# SimGEKI2_Side.net
KiCad netlist of a schematic drawn in EasyEDA Pro
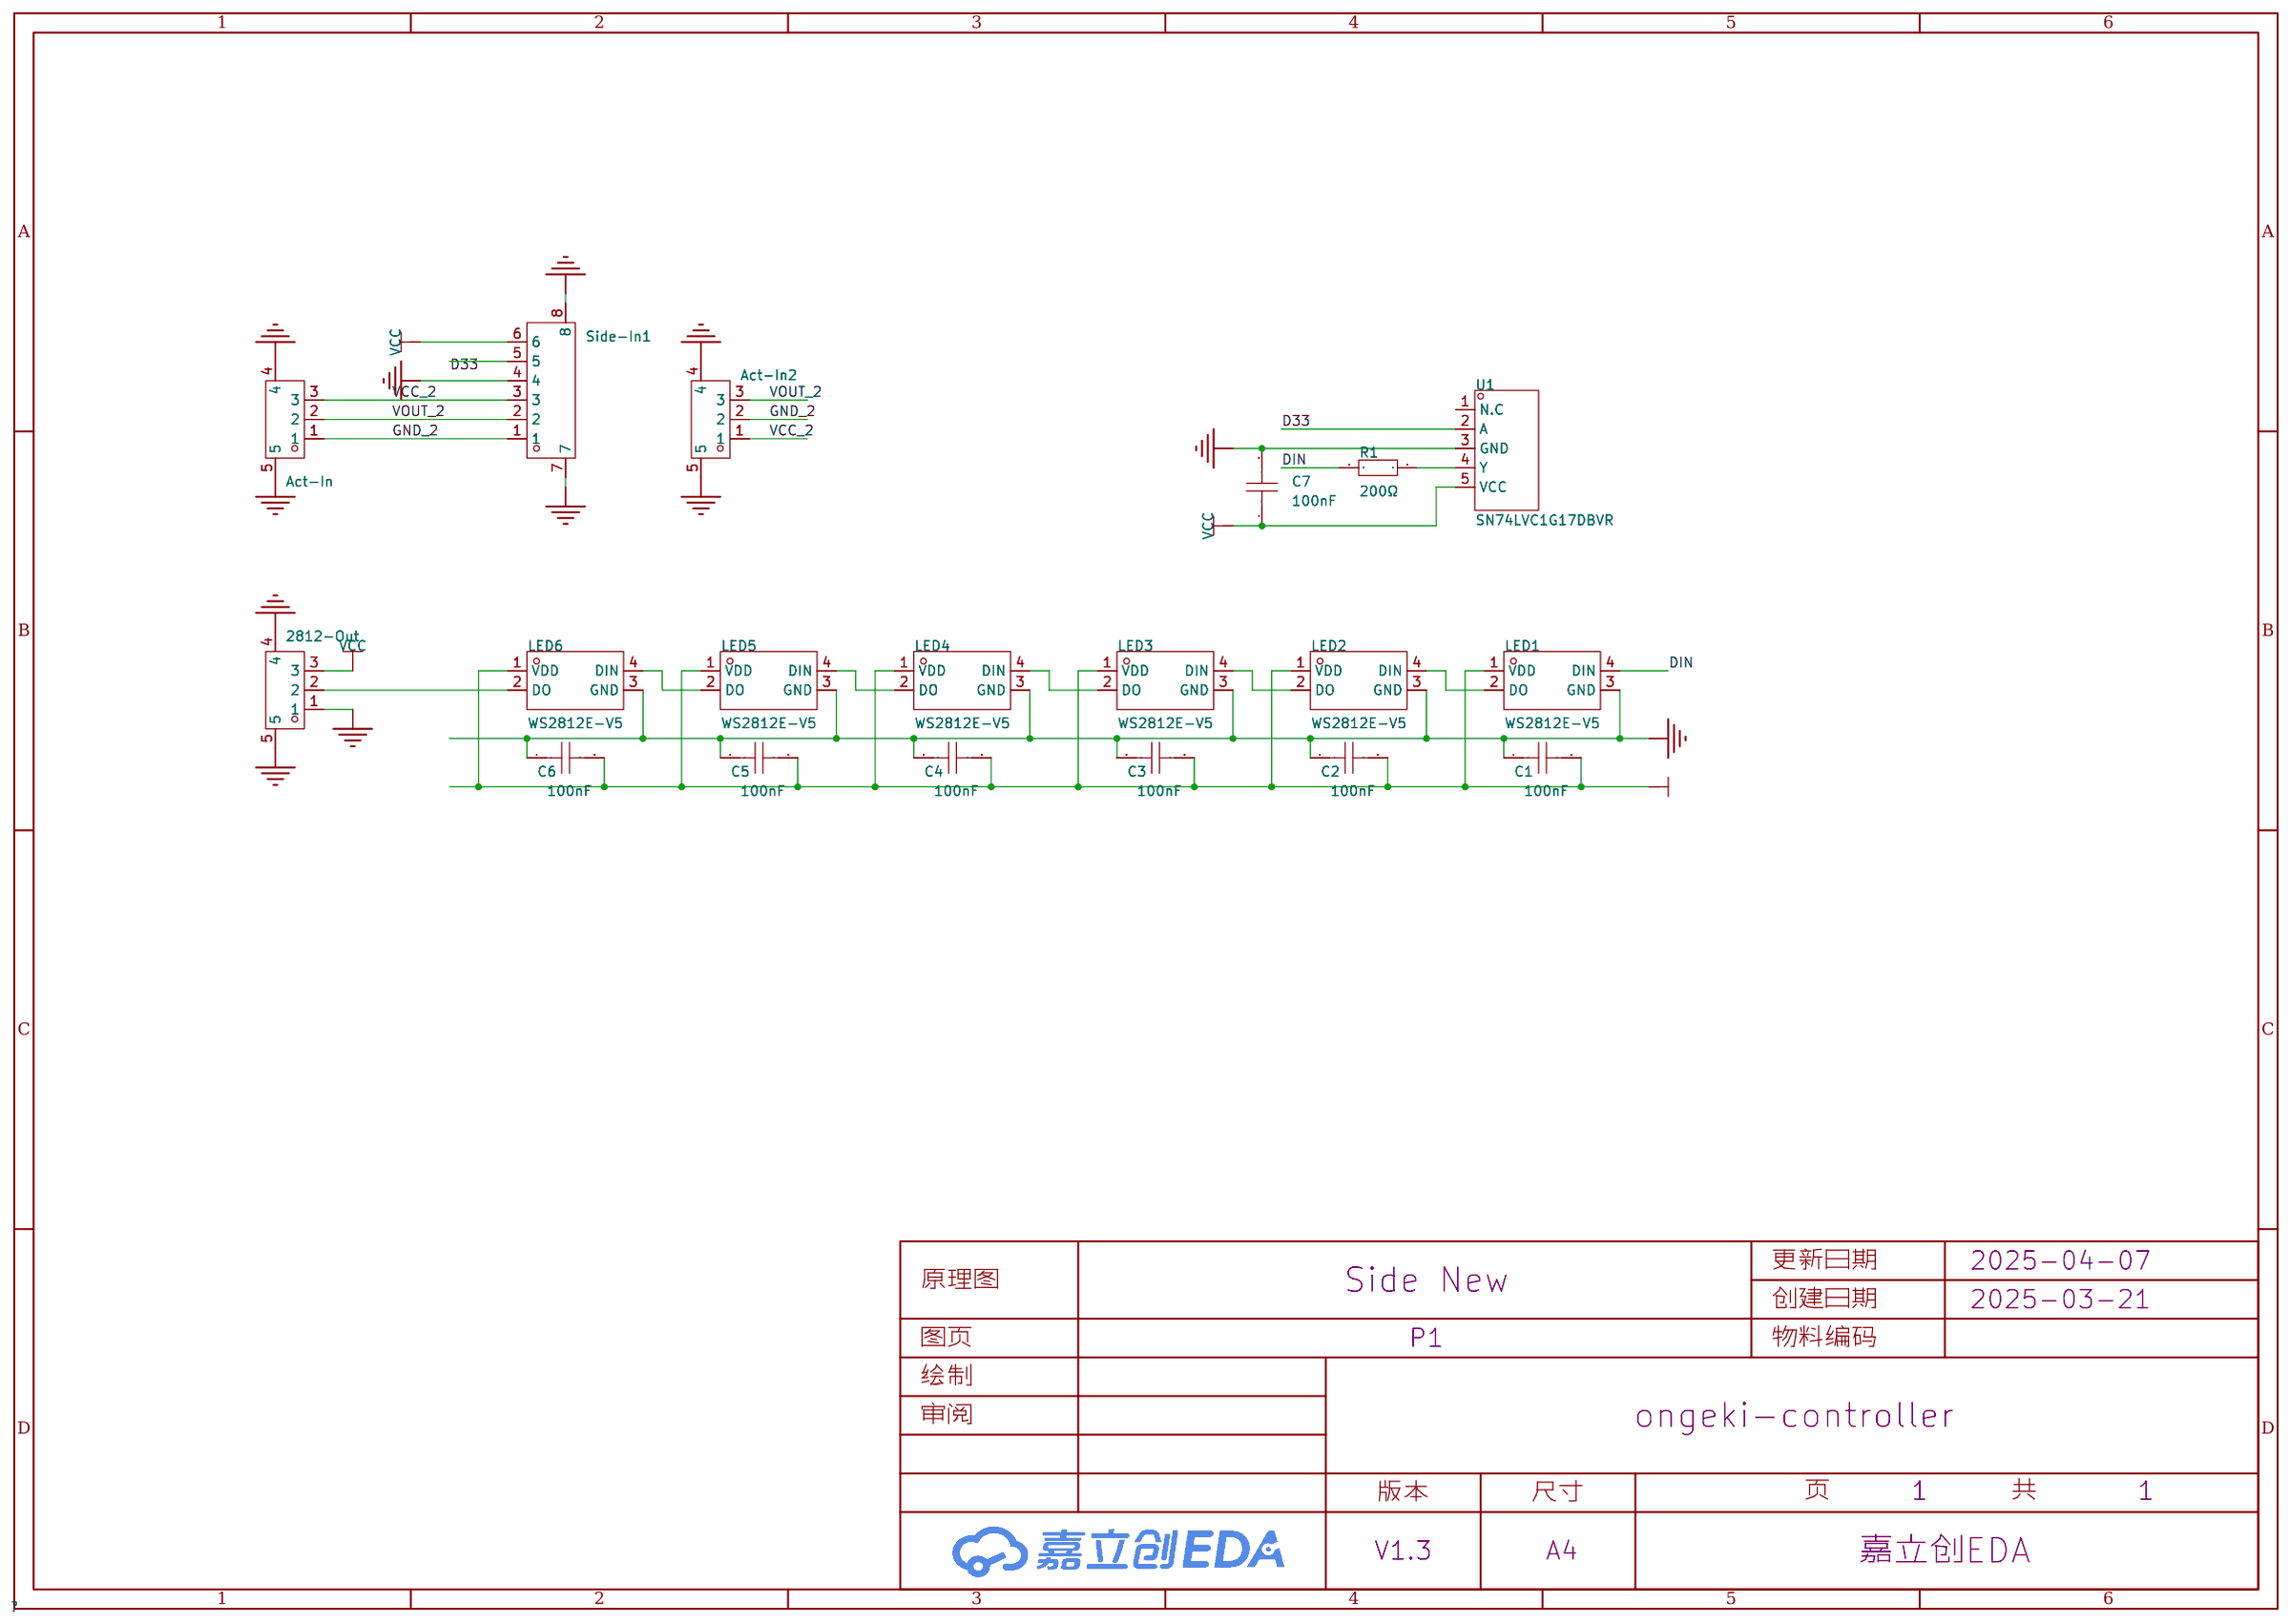
[diagram p0: schematic sheet]

(export (version "E")
  (design (tool "Eeschema 10.0.6"))
  (components
    (comp (ref "2812-Out")
      (value "WAFER-PH2.0-3PWB")
      (footprint "easyedapro:CONN-SMD_3P-P2.00_XUNPU_WAFER-PH2.0-3PWB")
      (description "插针结构:1x3P;间距:2mm;安装方式:卧贴;总PIN数:3P;排数:1;每排PIN数:3;额定电流:2A;工作温度范围:-25°C~+85°C;")
      (fields (field (name "Manufacturer") "XUNPU(讯普)"))
      (libsource (lib "easyedapro") (part "WAFER-PH2.0-3PWB"))
    )
    (comp (ref "Act-In")
      (value "WAFER-PH2.0-3PWB")
      (footprint "easyedapro:CONN-SMD_3P-P2.00_XUNPU_WAFER-PH2.0-3PWB")
      (description "插针结构:1x3P;间距:2mm;安装方式:卧贴;总PIN数:3P;排数:1;每排PIN数:3;额定电流:2A;工作温度范围:-25°C~+85°C;")
      (fields (field (name "Manufacturer") "XUNPU(讯普)"))
      (libsource (lib "easyedapro") (part "WAFER-PH2.0-3PWB"))
    )
    (comp (ref "Act-In2")
      (value "Act-In2")
      (footprint "easyedapro:CONN-SMD_3P-P2.50_BX-XH2.54-3PWT")
      (fields (field (name "Manufacturer") "Bossie(博锡)"))
      (libsource (lib "easyedapro") (part "BX-XH2.54-3PWT"))
    )
    (comp (ref "C1")
      (value "100nF")
      (footprint "easyedapro:C0603")
      (libsource (lib "easyedapro") (part "CapAcitance"))
    )
    (comp (ref "C2")
      (value "100nF")
      (footprint "easyedapro:C0603")
      (libsource (lib "easyedapro") (part "CapAcitance"))
    )
    (comp (ref "C3")
      (value "100nF")
      (footprint "easyedapro:C0603")
      (libsource (lib "easyedapro") (part "CapAcitance"))
    )
    (comp (ref "C4")
      (value "100nF")
      (footprint "easyedapro:C0603")
      (libsource (lib "easyedapro") (part "CapAcitance"))
    )
    (comp (ref "C5")
      (value "100nF")
      (footprint "easyedapro:C0603")
      (libsource (lib "easyedapro") (part "CapAcitance"))
    )
    (comp (ref "C6")
      (value "100nF")
      (footprint "easyedapro:C0603")
      (libsource (lib "easyedapro") (part "CapAcitance"))
    )
    (comp (ref "C7")
      (value "100nF")
      (footprint "easyedapro:C0603")
      (libsource (lib "easyedapro") (part "CapAcitance"))
    )
    (comp (ref "LED1")
      (value "WS2812E-V5")
      (footprint "easyedapro:LED-SMD_4P-L5.0-W5.0-LS5.4-TL-1")
      (description "发光颜色:RGB三色;功率:-;正向电流:12.5mA;主波长:623nm；451nm；523nm;二极管配置:-;透镜颜色:-;色温:-;发光角度:-;载带方式:-;工作温度:-;")
      (fields (field (name "Manufacturer") "worldsemi"))
      (libsource (lib "easyedapro") (part "WS2812E-V5"))
    )
    (comp (ref "LED2")
      (value "WS2812E-V5")
      (footprint "easyedapro:LED-SMD_4P-L5.0-W5.0-LS5.4-TL-1")
      (description "发光颜色:RGB三色;功率:-;正向电流:12.5mA;主波长:623nm；451nm；523nm;二极管配置:-;透镜颜色:-;色温:-;发光角度:-;载带方式:-;工作温度:-;")
      (fields (field (name "Manufacturer") "worldsemi"))
      (libsource (lib "easyedapro") (part "WS2812E-V5"))
    )
    (comp (ref "LED3")
      (value "WS2812E-V5")
      (footprint "easyedapro:LED-SMD_4P-L5.0-W5.0-LS5.4-TL-1")
      (description "发光颜色:RGB三色;功率:-;正向电流:12.5mA;主波长:623nm；451nm；523nm;二极管配置:-;透镜颜色:-;色温:-;发光角度:-;载带方式:-;工作温度:-;")
      (fields (field (name "Manufacturer") "worldsemi"))
      (libsource (lib "easyedapro") (part "WS2812E-V5"))
    )
    (comp (ref "LED4")
      (value "WS2812E-V5")
      (footprint "easyedapro:LED-SMD_4P-L5.0-W5.0-LS5.4-TL-1")
      (description "发光颜色:RGB三色;功率:-;正向电流:12.5mA;主波长:623nm；451nm；523nm;二极管配置:-;透镜颜色:-;色温:-;发光角度:-;载带方式:-;工作温度:-;")
      (fields (field (name "Manufacturer") "worldsemi"))
      (libsource (lib "easyedapro") (part "WS2812E-V5"))
    )
    (comp (ref "LED5")
      (value "WS2812E-V5")
      (footprint "easyedapro:LED-SMD_4P-L5.0-W5.0-LS5.4-TL-1")
      (description "发光颜色:RGB三色;功率:-;正向电流:12.5mA;主波长:623nm；451nm；523nm;二极管配置:-;透镜颜色:-;色温:-;发光角度:-;载带方式:-;工作温度:-;")
      (fields (field (name "Manufacturer") "worldsemi"))
      (libsource (lib "easyedapro") (part "WS2812E-V5"))
    )
    (comp (ref "LED6")
      (value "WS2812E-V5")
      (footprint "easyedapro:LED-SMD_4P-L5.0-W5.0-LS5.4-TL-1")
      (description "发光颜色:RGB三色;功率:-;正向电流:12.5mA;主波长:623nm；451nm；523nm;二极管配置:-;透镜颜色:-;色温:-;发光角度:-;载带方式:-;工作温度:-;")
      (fields (field (name "Manufacturer") "worldsemi"))
      (libsource (lib "easyedapro") (part "WS2812E-V5"))
    )
    (comp (ref "R1") (value "200Ω") (footprint "easyedapro:R0603") (libsource (lib "easyedapro") (part "电阻")))
    (comp (ref "Side-In1")
      (value "WAFER-PH2.0-6PWB")
      (footprint "easyedapro:CONN-SMD_6P-P2.00_XUNPU_WAFER-PH2.0-6PWB")
      (fields (field (name "Manufacturer") "XUNPU(讯普)"))
      (libsource (lib "easyedapro") (part "WAFER-PH2.0-6PWB"))
    )
    (comp (ref "U1")
      (value "SN74LVC1G17DBVR")
      (footprint "easyedapro:SOT-23-5_L3.0-W1.7-P0.95-LS2.8-BR")
      (description "输入类型:施密特触发器;电源电压:1.65V~5.5V;元件数:1;每个元件位数:1;灌电流(IOL):32mA;拉电流(IOH):32mA;")
      (fields (field (name "Manufacturer") "TI(德州仪器)"))
      (libsource (lib "easyedapro") (part "SN74LVC1G17DBVR"))
    )
  )
  (nets
    (net (code "1") (name "/D33") (class "Default")
      (node (ref "Side-In1") (pin "5") (pinfunction "5_5") (pintype "unspecified"))
      (node (ref "U1") (pin "2") (pinfunction "A_2") (pintype "input"))
    )
    (net (code "2") (name "/DIN") (class "Default")
      (node (ref "LED1") (pin "4") (pinfunction "DIN_4") (pintype "unspecified"))
      (node (ref "R1") (pin "1") (pinfunction "1_1") (pintype "input"))
    )
    (net (code "3") (name "/GND_2") (class "Default")
      (node (ref "Act-In") (pin "1") (pinfunction "1_1") (pintype "unspecified"))
      (node (ref "Act-In2") (pin "2") (pinfunction "2_2") (pintype "unspecified"))
      (node (ref "Side-In1") (pin "1") (pinfunction "1_1") (pintype "unspecified"))
    )
    (net (code "4") (name "/VCC_2") (class "Default")
      (node (ref "Act-In") (pin "3") (pinfunction "3_3") (pintype "unspecified"))
      (node (ref "Act-In2") (pin "1") (pinfunction "1_1") (pintype "unspecified"))
      (node (ref "Side-In1") (pin "3") (pinfunction "3_3") (pintype "unspecified"))
    )
    (net (code "5") (name "/VOUT_2") (class "Default")
      (node (ref "Act-In") (pin "2") (pinfunction "2_2") (pintype "unspecified"))
      (node (ref "Act-In2") (pin "3") (pinfunction "3_3") (pintype "unspecified"))
      (node (ref "Side-In1") (pin "2") (pinfunction "2_2") (pintype "unspecified"))
    )
    (net (code "6") (name "GND") (class "Default")
      (node (ref "2812-Out") (pin "1") (pinfunction "1_1") (pintype "unspecified"))
      (node (ref "2812-Out") (pin "4") (pinfunction "4_4") (pintype "unspecified"))
      (node (ref "2812-Out") (pin "5") (pinfunction "5_5") (pintype "unspecified"))
      (node (ref "Act-In") (pin "4") (pinfunction "4_4") (pintype "unspecified"))
      (node (ref "Act-In") (pin "5") (pinfunction "5_5") (pintype "unspecified"))
      (node (ref "Act-In2") (pin "4") (pinfunction "4_4") (pintype "unspecified"))
      (node (ref "Act-In2") (pin "5") (pinfunction "5_5") (pintype "unspecified"))
      (node (ref "C1") (pin "1") (pinfunction "1_1") (pintype "input"))
      (node (ref "C2") (pin "1") (pinfunction "1_1") (pintype "input"))
      (node (ref "C3") (pin "1") (pinfunction "1_1") (pintype "input"))
      (node (ref "C4") (pin "1") (pinfunction "1_1") (pintype "input"))
      (node (ref "C5") (pin "1") (pinfunction "1_1") (pintype "input"))
      (node (ref "C6") (pin "1") (pinfunction "1_1") (pintype "input"))
      (node (ref "C7") (pin "2") (pinfunction "2_2") (pintype "input"))
      (node (ref "LED1") (pin "3") (pinfunction "GND_3") (pintype "unspecified"))
      (node (ref "LED2") (pin "3") (pinfunction "GND_3") (pintype "unspecified"))
      (node (ref "LED3") (pin "3") (pinfunction "GND_3") (pintype "unspecified"))
      (node (ref "LED4") (pin "3") (pinfunction "GND_3") (pintype "unspecified"))
      (node (ref "LED5") (pin "3") (pinfunction "GND_3") (pintype "unspecified"))
      (node (ref "LED6") (pin "3") (pinfunction "GND_3") (pintype "unspecified"))
      (node (ref "Side-In1") (pin "4") (pinfunction "4_4") (pintype "unspecified"))
      (node (ref "Side-In1") (pin "7") (pinfunction "7_7") (pintype "unspecified"))
      (node (ref "Side-In1") (pin "8") (pinfunction "8_8") (pintype "unspecified"))
      (node (ref "U1") (pin "3") (pinfunction "GND_3") (pintype "input"))
    )
    (net (code "7") (name "Net-(LED1-DO)") (class "Default")
      (node (ref "LED1") (pin "2") (pinfunction "DO_2") (pintype "unspecified"))
      (node (ref "LED2") (pin "4") (pinfunction "DIN_4") (pintype "unspecified"))
    )
    (net (code "8") (name "Net-(LED2-DO)") (class "Default")
      (node (ref "LED2") (pin "2") (pinfunction "DO_2") (pintype "unspecified"))
      (node (ref "LED3") (pin "4") (pinfunction "DIN_4") (pintype "unspecified"))
    )
    (net (code "9") (name "Net-(LED3-DO)") (class "Default")
      (node (ref "LED3") (pin "2") (pinfunction "DO_2") (pintype "unspecified"))
      (node (ref "LED4") (pin "4") (pinfunction "DIN_4") (pintype "unspecified"))
    )
    (net (code "10") (name "Net-(LED4-DO)") (class "Default")
      (node (ref "LED4") (pin "2") (pinfunction "DO_2") (pintype "unspecified"))
      (node (ref "LED5") (pin "4") (pinfunction "DIN_4") (pintype "unspecified"))
    )
    (net (code "11") (name "Net-(LED5-DO)") (class "Default")
      (node (ref "LED5") (pin "2") (pinfunction "DO_2") (pintype "unspecified"))
      (node (ref "LED6") (pin "4") (pinfunction "DIN_4") (pintype "unspecified"))
    )
    (net (code "12") (name "Net-(LED6-DO)") (class "Default")
      (node (ref "2812-Out") (pin "2") (pinfunction "2_2") (pintype "unspecified"))
      (node (ref "LED6") (pin "2") (pinfunction "DO_2") (pintype "unspecified"))
    )
    (net (code "13") (name "Net-(U1-Y)") (class "Default")
      (node (ref "R1") (pin "2") (pinfunction "2_2") (pintype "input"))
      (node (ref "U1") (pin "4") (pinfunction "Y_4") (pintype "input"))
    )
    (net (code "14") (name "VCC") (class "Default")
      (node (ref "2812-Out") (pin "3") (pinfunction "3_3") (pintype "unspecified"))
      (node (ref "C1") (pin "2") (pinfunction "2_2") (pintype "input"))
      (node (ref "C2") (pin "2") (pinfunction "2_2") (pintype "input"))
      (node (ref "C3") (pin "2") (pinfunction "2_2") (pintype "input"))
      (node (ref "C4") (pin "2") (pinfunction "2_2") (pintype "input"))
      (node (ref "C5") (pin "2") (pinfunction "2_2") (pintype "input"))
      (node (ref "C6") (pin "2") (pinfunction "2_2") (pintype "input"))
      (node (ref "C7") (pin "1") (pinfunction "1_1") (pintype "input"))
      (node (ref "LED1") (pin "1") (pinfunction "VDD_1") (pintype "unspecified"))
      (node (ref "LED2") (pin "1") (pinfunction "VDD_1") (pintype "unspecified"))
      (node (ref "LED3") (pin "1") (pinfunction "VDD_1") (pintype "unspecified"))
      (node (ref "LED4") (pin "1") (pinfunction "VDD_1") (pintype "unspecified"))
      (node (ref "LED5") (pin "1") (pinfunction "VDD_1") (pintype "unspecified"))
      (node (ref "LED6") (pin "1") (pinfunction "VDD_1") (pintype "unspecified"))
      (node (ref "Side-In1") (pin "6") (pinfunction "6_6") (pintype "unspecified"))
      (node (ref "U1") (pin "5") (pinfunction "VCC_5") (pintype "input"))
    )
    (net (code "15") (name "unconnected-(U1-N.C-Pad1)") (class "Default")
      (node (ref "U1") (pin "1") (pinfunction "N.C_1") (pintype "input"))
    )
  )
)
